# MCU.net
KiCad netlist of a schematic drawn in Altium Designer
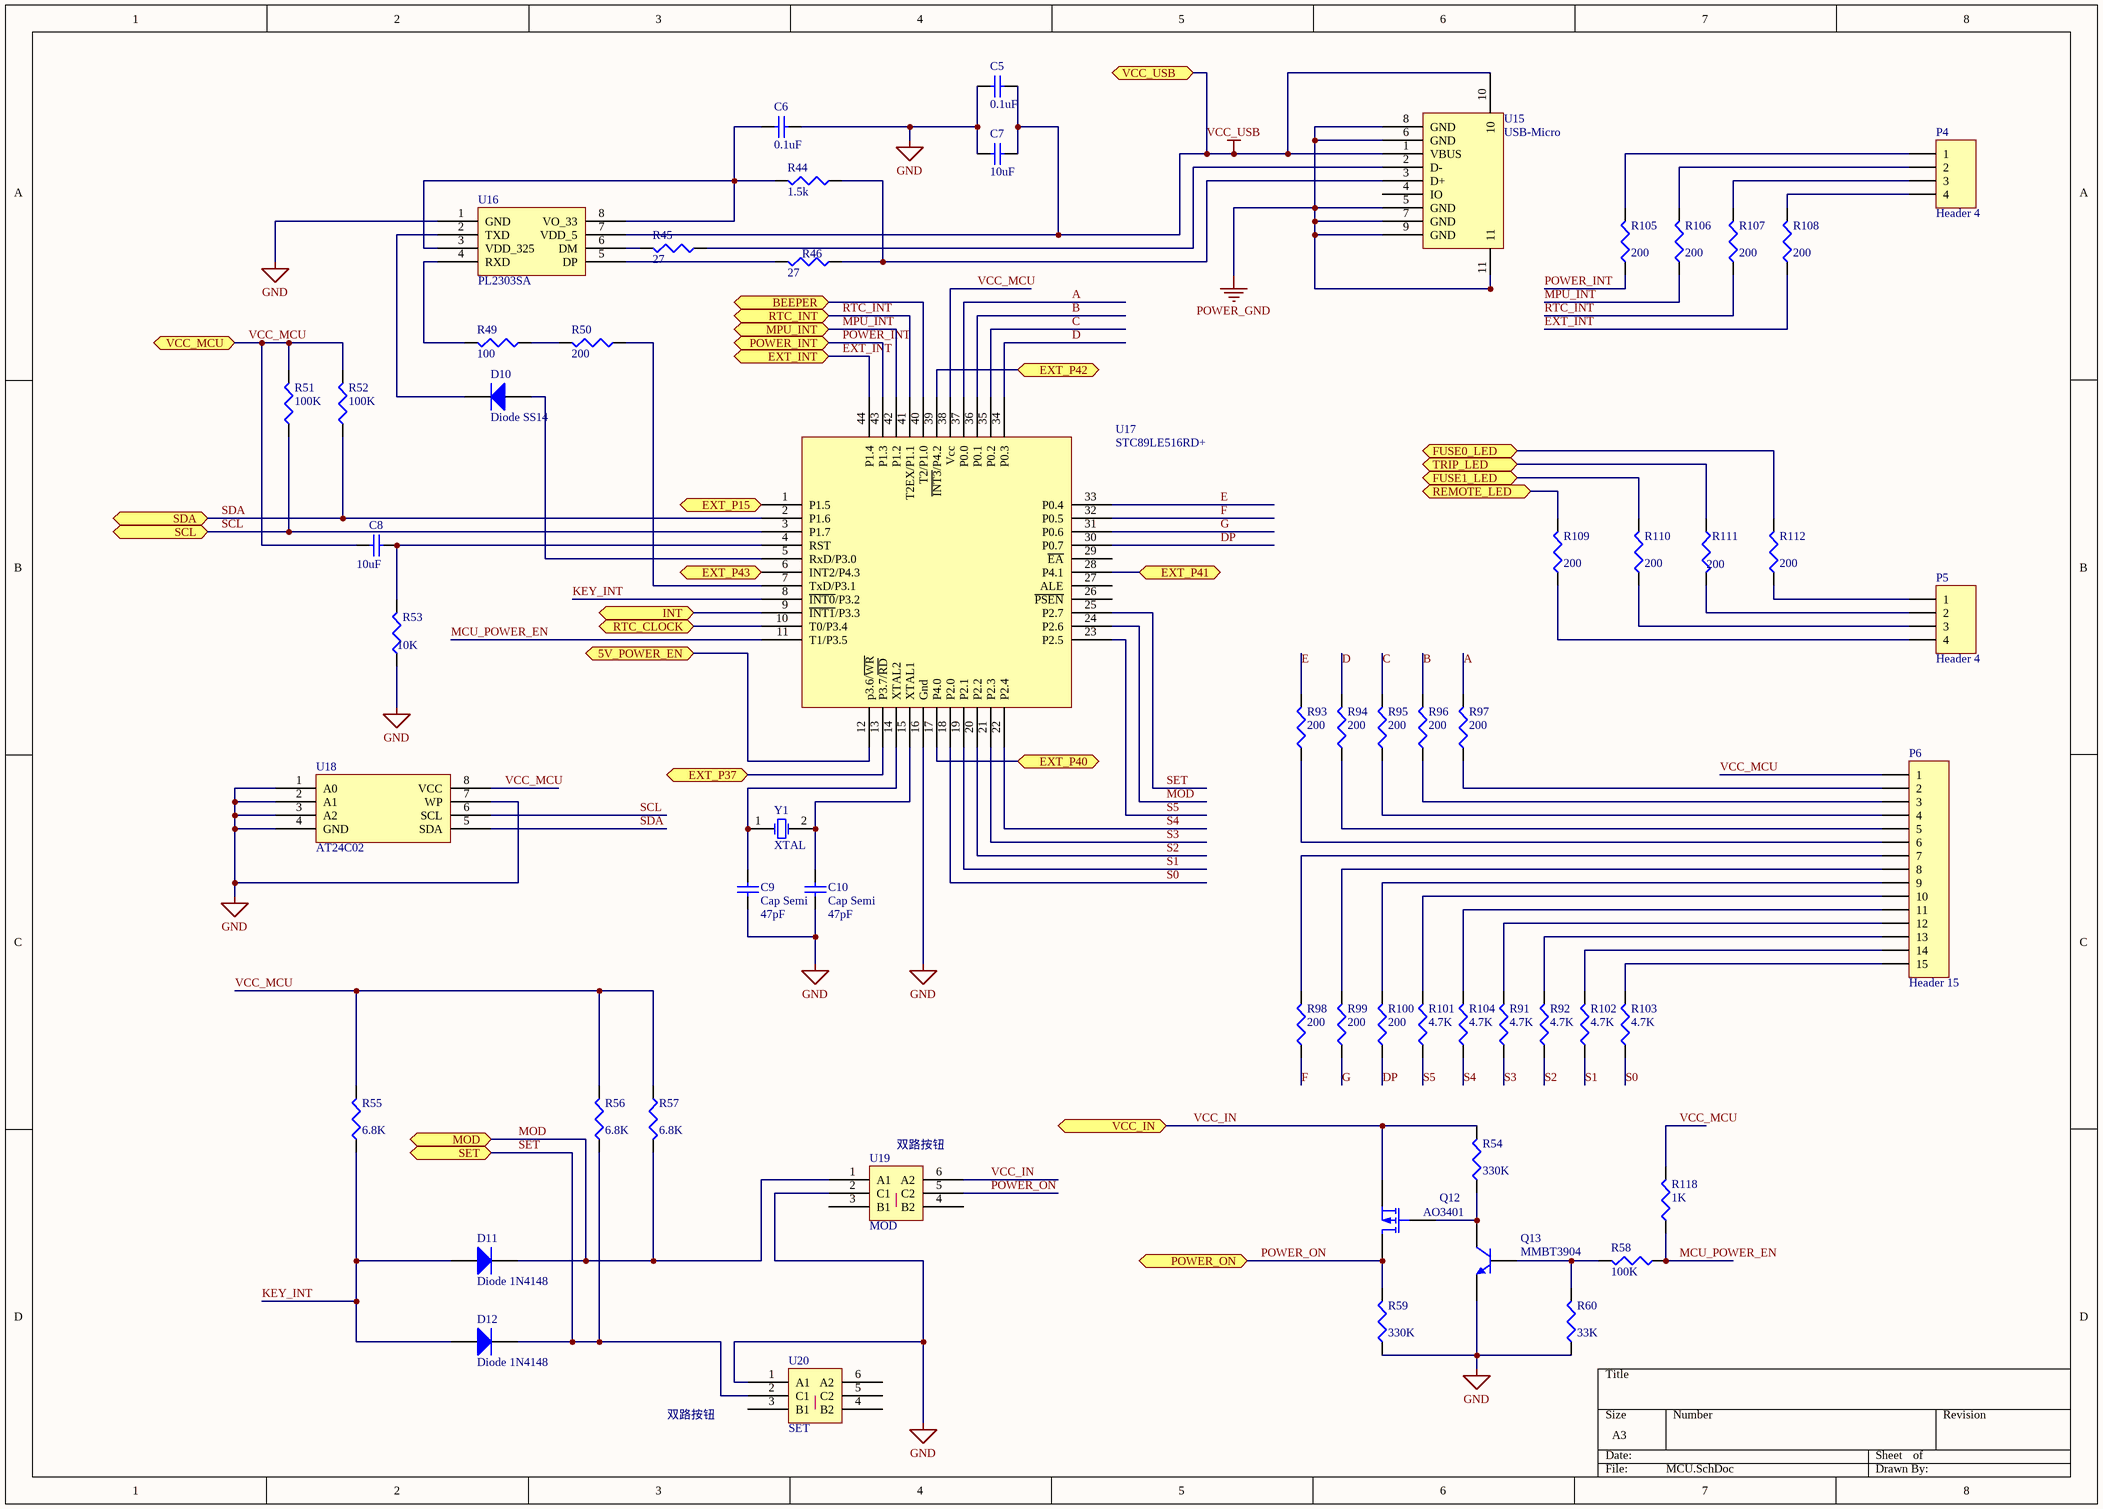
[diagram p0: MCU.SchDoc]

(export (version "E")
  (design (tool "Eeschema 10.0.6"))
  (components
    (comp (ref "C5")
      (value "0.1uF")
      (footprint "clock:0603")
      (description "Capacitor (Semiconductor SIM Model)")
      (fields (field (name "Comment") "Cap Semi") (field (name "PUBLISHER") "Altium Limited"))
      (libsource (lib "Miscellaneous Devices") (part "Cap Semi"))
    )
    (comp (ref "C6")
      (value "0.1uF")
      (footprint "clock:0603")
      (description "Capacitor (Semiconductor SIM Model)")
      (fields (field (name "Comment") "Cap Semi") (field (name "PUBLISHER") "Altium Limited"))
      (libsource (lib "Miscellaneous Devices") (part "Cap Semi"))
    )
    (comp (ref "C7")
      (value "10uF")
      (footprint "clock:0603")
      (description "Capacitor (Semiconductor SIM Model)")
      (fields (field (name "Comment") "Cap Semi") (field (name "PUBLISHER") "Altium Limited"))
      (libsource (lib "Miscellaneous Devices") (part "Cap Semi"))
    )
    (comp (ref "C8")
      (value "10uF")
      (footprint "clock:0603")
      (description "Capacitor (Semiconductor SIM Model)")
      (fields (field (name "Comment") "Cap Semi") (field (name "PUBLISHER") "Altium Limited"))
      (libsource (lib "Miscellaneous Devices") (part "Cap Semi"))
    )
    (comp (ref "C9")
      (value "Cap Semi")
      (footprint "clock:0603")
      (description "Capacitor (Semiconductor SIM Model)")
      (fields (field (name "ALTIUM_VALUE") "47pF") (field (name "PUBLISHER") "Altium Limited"))
      (libsource (lib "Miscellaneous Devices") (part "Cap Semi"))
    )
    (comp (ref "C10")
      (value "Cap Semi")
      (footprint "clock:0603")
      (description "Capacitor (Semiconductor SIM Model)")
      (fields (field (name "ALTIUM_VALUE") "47pF") (field (name "PUBLISHER") "Altium Limited"))
      (libsource (lib "Miscellaneous Devices") (part "Cap Semi"))
    )
    (comp (ref "D10")
      (value "Diode SS14")
      (footprint "clock:SMA")
      (description "1 Amp General Purpose Rectifier")
      (fields (field (name "PUBLISHER") "Altium Limited"))
      (libsource (lib "Miscellaneous Devices") (part "Diode 1N4005"))
    )
    (comp (ref "D11")
      (value "Diode 1N4148")
      (footprint "clock:1206D")
      (description "1 Amp General Purpose Rectifier")
      (fields (field (name "PUBLISHER") "Altium Limited"))
      (libsource (lib "Miscellaneous Devices") (part "Diode 1N4005"))
    )
    (comp (ref "D12")
      (value "Diode 1N4148")
      (footprint "clock:1206D")
      (description "1 Amp General Purpose Rectifier")
      (fields (field (name "PUBLISHER") "Altium Limited"))
      (libsource (lib "Miscellaneous Devices") (part "Diode 1N4005"))
    )
    (comp (ref "P4")
      (value "Header 4")
      (footprint "HDR1X4")
      (description "Header, 4-Pin")
      (fields (field (name "PUBLISHER") "Altium Limited"))
      (libsource (lib "Miscellaneous Connectors") (part "Header 4"))
    )
    (comp (ref "P5")
      (value "Header 4")
      (footprint "HDR1X4")
      (description "Header, 4-Pin")
      (fields (field (name "PUBLISHER") "Altium Limited"))
      (libsource (lib "Miscellaneous Connectors") (part "Header 4"))
    )
    (comp (ref "P6")
      (value "Header 15")
      (footprint "clock:HDR1X15")
      (description "Header, 15-Pin")
      (fields (field (name "PUBLISHER") "Altium Limited"))
      (libsource (lib "Miscellaneous Connectors") (part "Header 15"))
    )
    (comp (ref "Q12")
      (value "AO3401")
      (footprint "clock:SOT23-3-PMOS")
      (description "P-Channel MOSFET")
      (fields (field (name "PUBLISHER") "Altium Limited"))
      (libsource (lib "Miscellaneous Devices") (part "MOSFET-P"))
    )
    (comp (ref "Q13")
      (value "MMBT3904")
      (footprint "clock:SOT23-3-NPN")
      (description "NPN General Purpose Amplifier")
      (fields (field (name "PUBLISHER") "Altium Limited"))
      (libsource (lib "Miscellaneous Devices") (part "2N3904"))
    )
    (comp (ref "R44")
      (value "1.5k")
      (footprint "clock:0603")
      (description "Resistor")
      (fields (field (name "Comment") "Res3") (field (name "PUBLISHER") "Altium Limited"))
      (libsource (lib "Miscellaneous Devices") (part "Res3"))
    )
    (comp (ref "R45")
      (value "27")
      (footprint "clock:0603")
      (description "Resistor")
      (fields (field (name "Comment") "Res3") (field (name "PUBLISHER") "Altium Limited"))
      (libsource (lib "Miscellaneous Devices") (part "Res3"))
    )
    (comp (ref "R46")
      (value "27")
      (footprint "clock:0603")
      (description "Resistor")
      (fields (field (name "Comment") "Res3") (field (name "PUBLISHER") "Altium Limited"))
      (libsource (lib "Miscellaneous Devices") (part "Res3"))
    )
    (comp (ref "R49")
      (value "100")
      (footprint "clock:0603")
      (description "Resistor")
      (fields (field (name "Comment") "Res3") (field (name "PUBLISHER") "Altium Limited"))
      (libsource (lib "Miscellaneous Devices") (part "Res3"))
    )
    (comp (ref "R50")
      (value "200")
      (footprint "clock:0603")
      (description "Resistor")
      (fields (field (name "Comment") "Res3") (field (name "PUBLISHER") "Altium Limited"))
      (libsource (lib "Miscellaneous Devices") (part "Res3"))
    )
    (comp (ref "R51")
      (value "100K")
      (footprint "clock:0603")
      (description "Resistor")
      (fields (field (name "Comment") "Res3") (field (name "PUBLISHER") "Altium Limited"))
      (libsource (lib "Miscellaneous Devices") (part "Res3"))
    )
    (comp (ref "R52")
      (value "100K")
      (footprint "clock:0603")
      (description "Resistor")
      (fields (field (name "Comment") "Res3") (field (name "PUBLISHER") "Altium Limited"))
      (libsource (lib "Miscellaneous Devices") (part "Res3"))
    )
    (comp (ref "R53")
      (value "10K")
      (footprint "clock:0603")
      (description "Resistor")
      (fields (field (name "Comment") "Res3") (field (name "PUBLISHER") "Altium Limited"))
      (libsource (lib "Miscellaneous Devices") (part "Res3"))
    )
    (comp (ref "R54")
      (value "330K")
      (footprint "clock:0603")
      (description "Resistor")
      (fields (field (name "Comment") "Res3") (field (name "PUBLISHER") "Altium Limited"))
      (libsource (lib "Miscellaneous Devices") (part "Res3"))
    )
    (comp (ref "R55")
      (value "6.8K")
      (footprint "clock:0603")
      (description "Resistor")
      (fields (field (name "Comment") "Res3") (field (name "PUBLISHER") "Altium Limited"))
      (libsource (lib "Miscellaneous Devices") (part "Res3"))
    )
    (comp (ref "R56")
      (value "6.8K")
      (footprint "clock:0603")
      (description "Resistor")
      (fields (field (name "Comment") "Res3") (field (name "PUBLISHER") "Altium Limited"))
      (libsource (lib "Miscellaneous Devices") (part "Res3"))
    )
    (comp (ref "R57")
      (value "6.8K")
      (footprint "clock:0603")
      (description "Resistor")
      (fields (field (name "Comment") "Res3") (field (name "PUBLISHER") "Altium Limited"))
      (libsource (lib "Miscellaneous Devices") (part "Res3"))
    )
    (comp (ref "R58")
      (value "100K")
      (footprint "clock:0603")
      (description "Resistor")
      (fields (field (name "Comment") "Res3") (field (name "PUBLISHER") "Altium Limited"))
      (libsource (lib "Miscellaneous Devices") (part "Res3"))
    )
    (comp (ref "R59")
      (value "330K")
      (footprint "clock:0603")
      (description "Resistor")
      (fields (field (name "Comment") "Res3") (field (name "PUBLISHER") "Altium Limited"))
      (libsource (lib "Miscellaneous Devices") (part "Res3"))
    )
    (comp (ref "R60")
      (value "33K")
      (footprint "clock:0603")
      (description "Resistor")
      (fields (field (name "Comment") "Res3") (field (name "PUBLISHER") "Altium Limited"))
      (libsource (lib "Miscellaneous Devices") (part "Res3"))
    )
    (comp (ref "R91")
      (value "4.7K")
      (footprint "clock:0603")
      (description "Resistor")
      (fields (field (name "Comment") "Res3") (field (name "PUBLISHER") "Altium Limited"))
      (libsource (lib "Miscellaneous Devices") (part "Res3"))
    )
    (comp (ref "R92")
      (value "4.7K")
      (footprint "clock:0603")
      (description "Resistor")
      (fields (field (name "Comment") "Res3") (field (name "PUBLISHER") "Altium Limited"))
      (libsource (lib "Miscellaneous Devices") (part "Res3"))
    )
    (comp (ref "R93")
      (value "200")
      (footprint "clock:0603")
      (description "Resistor")
      (fields (field (name "Comment") "Res3") (field (name "PUBLISHER") "Altium Limited"))
      (libsource (lib "Miscellaneous Devices") (part "Res3"))
    )
    (comp (ref "R94")
      (value "200")
      (footprint "clock:0603")
      (description "Resistor")
      (fields (field (name "Comment") "Res3") (field (name "PUBLISHER") "Altium Limited"))
      (libsource (lib "Miscellaneous Devices") (part "Res3"))
    )
    (comp (ref "R95")
      (value "200")
      (footprint "clock:0603")
      (description "Resistor")
      (fields (field (name "Comment") "Res3") (field (name "PUBLISHER") "Altium Limited"))
      (libsource (lib "Miscellaneous Devices") (part "Res3"))
    )
    (comp (ref "R96")
      (value "200")
      (footprint "clock:0603")
      (description "Resistor")
      (fields (field (name "Comment") "Res3") (field (name "PUBLISHER") "Altium Limited"))
      (libsource (lib "Miscellaneous Devices") (part "Res3"))
    )
    (comp (ref "R97")
      (value "200")
      (footprint "clock:0603")
      (description "Resistor")
      (fields (field (name "Comment") "Res3") (field (name "PUBLISHER") "Altium Limited"))
      (libsource (lib "Miscellaneous Devices") (part "Res3"))
    )
    (comp (ref "R98")
      (value "200")
      (footprint "clock:0603")
      (description "Resistor")
      (fields (field (name "Comment") "Res3") (field (name "PUBLISHER") "Altium Limited"))
      (libsource (lib "Miscellaneous Devices") (part "Res3"))
    )
    (comp (ref "R99")
      (value "200")
      (footprint "clock:0603")
      (description "Resistor")
      (fields (field (name "Comment") "Res3") (field (name "PUBLISHER") "Altium Limited"))
      (libsource (lib "Miscellaneous Devices") (part "Res3"))
    )
    (comp (ref "R100")
      (value "200")
      (footprint "clock:0603")
      (description "Resistor")
      (fields (field (name "Comment") "Res3") (field (name "PUBLISHER") "Altium Limited"))
      (libsource (lib "Miscellaneous Devices") (part "Res3"))
    )
    (comp (ref "R101")
      (value "4.7K")
      (footprint "clock:0603")
      (description "Resistor")
      (fields (field (name "Comment") "Res3") (field (name "PUBLISHER") "Altium Limited"))
      (libsource (lib "Miscellaneous Devices") (part "Res3"))
    )
    (comp (ref "R102")
      (value "4.7K")
      (footprint "clock:0603")
      (description "Resistor")
      (fields (field (name "Comment") "Res3") (field (name "PUBLISHER") "Altium Limited"))
      (libsource (lib "Miscellaneous Devices") (part "Res3"))
    )
    (comp (ref "R103")
      (value "4.7K")
      (footprint "clock:0603")
      (description "Resistor")
      (fields (field (name "Comment") "Res3") (field (name "PUBLISHER") "Altium Limited"))
      (libsource (lib "Miscellaneous Devices") (part "Res3"))
    )
    (comp (ref "R104")
      (value "4.7K")
      (footprint "clock:0603")
      (description "Resistor")
      (fields (field (name "Comment") "Res3") (field (name "PUBLISHER") "Altium Limited"))
      (libsource (lib "Miscellaneous Devices") (part "Res3"))
    )
    (comp (ref "R105")
      (value "200")
      (footprint "clock:0603")
      (description "Resistor")
      (fields (field (name "Comment") "Res3") (field (name "PUBLISHER") "Altium Limited"))
      (libsource (lib "Miscellaneous Devices") (part "Res3"))
    )
    (comp (ref "R106")
      (value "200")
      (footprint "clock:0603")
      (description "Resistor")
      (fields (field (name "Comment") "Res3") (field (name "PUBLISHER") "Altium Limited"))
      (libsource (lib "Miscellaneous Devices") (part "Res3"))
    )
    (comp (ref "R107")
      (value "200")
      (footprint "clock:0603")
      (description "Resistor")
      (fields (field (name "Comment") "Res3") (field (name "PUBLISHER") "Altium Limited"))
      (libsource (lib "Miscellaneous Devices") (part "Res3"))
    )
    (comp (ref "R108")
      (value "200")
      (footprint "clock:0603")
      (description "Resistor")
      (fields (field (name "Comment") "Res3") (field (name "PUBLISHER") "Altium Limited"))
      (libsource (lib "Miscellaneous Devices") (part "Res3"))
    )
    (comp (ref "R109")
      (value "200")
      (footprint "clock:0603")
      (description "Resistor")
      (fields (field (name "Comment") "Res3") (field (name "PUBLISHER") "Altium Limited"))
      (libsource (lib "Miscellaneous Devices") (part "Res3"))
    )
    (comp (ref "R110")
      (value "200")
      (footprint "clock:0603")
      (description "Resistor")
      (fields (field (name "Comment") "Res3") (field (name "PUBLISHER") "Altium Limited"))
      (libsource (lib "Miscellaneous Devices") (part "Res3"))
    )
    (comp (ref "R111")
      (value "200")
      (footprint "clock:0603")
      (description "Resistor")
      (fields (field (name "Comment") "Res3") (field (name "PUBLISHER") "Altium Limited"))
      (libsource (lib "Miscellaneous Devices") (part "Res3"))
    )
    (comp (ref "R112")
      (value "200")
      (footprint "clock:0603")
      (description "Resistor")
      (fields (field (name "Comment") "Res3") (field (name "PUBLISHER") "Altium Limited"))
      (libsource (lib "Miscellaneous Devices") (part "Res3"))
    )
    (comp (ref "R118")
      (value "1K")
      (footprint "clock:0603")
      (description "Resistor")
      (fields (field (name "Comment") "Res3") (field (name "PUBLISHER") "Altium Limited"))
      (libsource (lib "Miscellaneous Devices") (part "Res3"))
    )
    (comp (ref "U15")
      (value "USB-Micro")
      (footprint "clock:USB-Micro")
      (libsource (lib "clock") (part "USB-Micro"))
    )
    (comp (ref "U16") (value "PL2303SA") (footprint "clock:SOP8") (libsource (lib "clock") (part "PL2303SA")))
    (comp (ref "U17")
      (value "STC89LE516RD+")
      (footprint "clock:LQFP44")
      (libsource (lib "clock") (part "STC89LE516RD+"))
    )
    (comp (ref "U18") (value "AT24C02") (footprint "clock:SOP8") (libsource (lib "clock") (part "AT24C02")))
    (comp (ref "U19") (value "MOD") (footprint "clock:HDR2X3") (libsource (lib "clock") (part "BUTTON")))
    (comp (ref "U20") (value "SET") (footprint "clock:HDR2X3") (libsource (lib "clock") (part "BUTTON")))
    (comp (ref "Y1")
      (value "XTAL")
      (footprint "clock:XTAL")
      (description "Crystal Oscillator")
      (fields (field (name "PUBLISHER") "Altium Limited"))
      (libsource (lib "Miscellaneous Devices") (part "XTAL"))
    )
  )
  (nets
    (net (code "1") (name "/5V_POWER_EN") (class "Default")
      (node (ref "U17") (pin "12") (pinfunction "p3.6/~{WR}_12") (pintype "passive"))
    )
    (net (code "2") (name "/A") (class "Default")
      (node (ref "R97") (pin "2") (pinfunction "2_2") (pintype "passive"))
      (node (ref "U17") (pin "37") (pinfunction "P0.0_37") (pintype "passive"))
    )
    (net (code "3") (name "/B") (class "Default")
      (node (ref "R96") (pin "2") (pinfunction "2_2") (pintype "passive"))
      (node (ref "U17") (pin "36") (pinfunction "P0.1_36") (pintype "passive"))
    )
    (net (code "4") (name "/BEEPER") (class "Default")
      (node (ref "U17") (pin "40") (pinfunction "T2/P1.0_40") (pintype "passive"))
    )
    (net (code "5") (name "/C") (class "Default")
      (node (ref "R95") (pin "2") (pinfunction "2_2") (pintype "passive"))
      (node (ref "U17") (pin "35") (pinfunction "P0.2_35") (pintype "passive"))
    )
    (net (code "6") (name "/D") (class "Default")
      (node (ref "R94") (pin "2") (pinfunction "2_2") (pintype "passive"))
      (node (ref "U17") (pin "34") (pinfunction "P0.3_34") (pintype "passive"))
    )
    (net (code "7") (name "/DP") (class "Default")
      (node (ref "R100") (pin "1") (pinfunction "1_1") (pintype "passive"))
      (node (ref "U17") (pin "30") (pinfunction "P0.7_30") (pintype "passive"))
    )
    (net (code "8") (name "/E") (class "Default")
      (node (ref "R93") (pin "2") (pinfunction "2_2") (pintype "passive"))
      (node (ref "U17") (pin "33") (pinfunction "P0.4_33") (pintype "passive"))
    )
    (net (code "9") (name "/EXT_INT") (class "Default")
      (node (ref "R108") (pin "1") (pinfunction "1_1") (pintype "passive"))
      (node (ref "U17") (pin "44") (pinfunction "P1.4_44") (pintype "passive"))
    )
    (net (code "10") (name "/EXT_P15") (class "Default")
      (node (ref "U17") (pin "1") (pinfunction "P1.5_1") (pintype "passive"))
    )
    (net (code "11") (name "/EXT_P37") (class "Default")
      (node (ref "U17") (pin "13") (pinfunction "P3.7/~{RD}_13") (pintype "passive"))
    )
    (net (code "12") (name "/EXT_P40") (class "Default")
      (node (ref "U17") (pin "17") (pinfunction "P4.0_17") (pintype "passive"))
    )
    (net (code "13") (name "/EXT_P41") (class "Default")
      (node (ref "U17") (pin "28") (pinfunction "P4.1_28") (pintype "passive"))
    )
    (net (code "14") (name "/EXT_P42") (class "Default")
      (node (ref "U17") (pin "39") (pinfunction "~{INT3}/P4.2_39") (pintype "passive"))
    )
    (net (code "15") (name "/EXT_P43") (class "Default")
      (node (ref "U17") (pin "6") (pinfunction "INT2/P4.3_6") (pintype "passive"))
    )
    (net (code "16") (name "/F") (class "Default")
      (node (ref "R98") (pin "1") (pinfunction "1_1") (pintype "passive"))
      (node (ref "U17") (pin "32") (pinfunction "P0.5_32") (pintype "passive"))
    )
    (net (code "17") (name "/FUSE0_LED") (class "Default")
      (node (ref "R112") (pin "2") (pinfunction "2_2") (pintype "passive"))
    )
    (net (code "18") (name "/FUSE1_LED") (class "Default")
      (node (ref "R110") (pin "2") (pinfunction "2_2") (pintype "passive"))
    )
    (net (code "19") (name "/G") (class "Default")
      (node (ref "R99") (pin "1") (pinfunction "1_1") (pintype "passive"))
      (node (ref "U17") (pin "31") (pinfunction "P0.6_31") (pintype "passive"))
    )
    (net (code "20") (name "/INT") (class "Default")
      (node (ref "U17") (pin "9") (pinfunction "~{INT1}/P3.3_9") (pintype "passive"))
    )
    (net (code "21") (name "/KEY_INT") (class "Default")
      (node (ref "D11") (pin "1") (pinfunction "A_1") (pintype "passive"))
      (node (ref "D12") (pin "1") (pinfunction "A_1") (pintype "passive"))
      (node (ref "R55") (pin "1") (pinfunction "1_1") (pintype "passive"))
      (node (ref "U17") (pin "8") (pinfunction "~{INT0}/P3.2_8") (pintype "passive"))
    )
    (net (code "22") (name "/MCU_POWER_EN") (class "Default")
      (node (ref "R118") (pin "1") (pinfunction "1_1") (pintype "passive"))
      (node (ref "R58") (pin "1") (pinfunction "1_1") (pintype "passive"))
      (node (ref "U17") (pin "11") (pinfunction "T1/P3.5_11") (pintype "passive"))
    )
    (net (code "23") (name "/MOD") (class "Default")
      (node (ref "D11") (pin "2") (pinfunction "K_2") (pintype "passive"))
      (node (ref "R57") (pin "2") (pinfunction "2_2") (pintype "passive"))
      (node (ref "U17") (pin "24") (pinfunction "P2.6_24") (pintype "passive"))
      (node (ref "U19") (pin "1") (pinfunction "A1_1") (pintype "passive"))
    )
    (net (code "24") (name "/MPU_INT") (class "Default")
      (node (ref "R106") (pin "1") (pinfunction "1_1") (pintype "passive"))
      (node (ref "U17") (pin "42") (pinfunction "P1.2_42") (pintype "passive"))
    )
    (net (code "25") (name "/POWER_INT") (class "Default")
      (node (ref "R105") (pin "1") (pinfunction "1_1") (pintype "passive"))
      (node (ref "U17") (pin "43") (pinfunction "P1.3_43") (pintype "passive"))
    )
    (net (code "26") (name "/POWER_ON") (class "Default")
      (node (ref "Q12") (pin "1") (pinfunction "D_1") (pintype "passive"))
      (node (ref "R59") (pin "2") (pinfunction "2_2") (pintype "passive"))
      (node (ref "U19") (pin "5") (pinfunction "C2_5") (pintype "passive"))
    )
    (net (code "27") (name "/REMOTE_LED") (class "Default")
      (node (ref "R109") (pin "2") (pinfunction "2_2") (pintype "passive"))
    )
    (net (code "28") (name "/RTC_CLOCK") (class "Default")
      (node (ref "U17") (pin "10") (pinfunction "T0/P3.4_10") (pintype "passive"))
    )
    (net (code "29") (name "/RTC_INT") (class "Default")
      (node (ref "R107") (pin "1") (pinfunction "1_1") (pintype "passive"))
      (node (ref "U17") (pin "41") (pinfunction "T2EX/P1.1_41") (pintype "passive"))
    )
    (net (code "30") (name "/S0") (class "Default")
      (node (ref "R103") (pin "1") (pinfunction "1_1") (pintype "passive"))
      (node (ref "U17") (pin "18") (pinfunction "P2.0_18") (pintype "passive"))
    )
    (net (code "31") (name "/S1") (class "Default")
      (node (ref "R102") (pin "1") (pinfunction "1_1") (pintype "passive"))
      (node (ref "U17") (pin "19") (pinfunction "P2.1_19") (pintype "passive"))
    )
    (net (code "32") (name "/S2") (class "Default")
      (node (ref "R92") (pin "1") (pinfunction "1_1") (pintype "passive"))
      (node (ref "U17") (pin "20") (pinfunction "P2.2_20") (pintype "passive"))
    )
    (net (code "33") (name "/S3") (class "Default")
      (node (ref "R91") (pin "1") (pinfunction "1_1") (pintype "passive"))
      (node (ref "U17") (pin "21") (pinfunction "P2.3_21") (pintype "passive"))
    )
    (net (code "34") (name "/S4") (class "Default")
      (node (ref "R104") (pin "1") (pinfunction "1_1") (pintype "passive"))
      (node (ref "U17") (pin "22") (pinfunction "P2.4_22") (pintype "passive"))
    )
    (net (code "35") (name "/S5") (class "Default")
      (node (ref "R101") (pin "1") (pinfunction "1_1") (pintype "passive"))
      (node (ref "U17") (pin "23") (pinfunction "P2.5_23") (pintype "passive"))
    )
    (net (code "36") (name "/SCL") (class "Default")
      (node (ref "R51") (pin "1") (pinfunction "1_1") (pintype "passive"))
      (node (ref "U17") (pin "3") (pinfunction "P1.7_3") (pintype "passive"))
      (node (ref "U18") (pin "6") (pinfunction "SCL_6") (pintype "passive"))
    )
    (net (code "37") (name "/SDA") (class "Default")
      (node (ref "R52") (pin "1") (pinfunction "1_1") (pintype "passive"))
      (node (ref "U17") (pin "2") (pinfunction "P1.6_2") (pintype "passive"))
      (node (ref "U18") (pin "5") (pinfunction "SDA_5") (pintype "passive"))
    )
    (net (code "38") (name "/SET") (class "Default")
      (node (ref "D12") (pin "2") (pinfunction "K_2") (pintype "passive"))
      (node (ref "R56") (pin "1") (pinfunction "1_1") (pintype "passive"))
      (node (ref "U17") (pin "25") (pinfunction "P2.7_25") (pintype "passive"))
      (node (ref "U20") (pin "2") (pinfunction "C1_2") (pintype "passive"))
    )
    (net (code "39") (name "/TRIP_LED") (class "Default")
      (node (ref "R111") (pin "1") (pinfunction "1_1") (pintype "passive"))
    )
    (net (code "40") (name "/VCC_IN") (class "Default")
      (node (ref "Q12") (pin "3") (pinfunction "S_3") (pintype "passive"))
      (node (ref "R54") (pin "2") (pinfunction "2_2") (pintype "passive"))
      (node (ref "U19") (pin "6") (pinfunction "A2_6") (pintype "passive"))
    )
    (net (code "41") (name "/VCC_MCU") (class "Default")
      (node (ref "C8") (pin "2") (pinfunction "2_2") (pintype "passive"))
      (node (ref "P6") (pin "1") (pinfunction "1_1") (pintype "passive"))
      (node (ref "R118") (pin "2") (pinfunction "2_2") (pintype "passive"))
      (node (ref "R51") (pin "2") (pinfunction "2_2") (pintype "passive"))
      (node (ref "R52") (pin "2") (pinfunction "2_2") (pintype "passive"))
      (node (ref "R55") (pin "2") (pinfunction "2_2") (pintype "passive"))
      (node (ref "R56") (pin "2") (pinfunction "2_2") (pintype "passive"))
      (node (ref "R57") (pin "1") (pinfunction "1_1") (pintype "passive"))
      (node (ref "U17") (pin "38") (pinfunction "Vcc_38") (pintype "passive"))
      (node (ref "U18") (pin "8") (pinfunction "VCC_8") (pintype "passive"))
    )
    (net (code "42") (name "GND") (class "Default")
      (node (ref "C10") (pin "1") (pinfunction "1_1") (pintype "passive"))
      (node (ref "C5") (pin "1") (pinfunction "1_1") (pintype "passive"))
      (node (ref "C6") (pin "2") (pinfunction "2_2") (pintype "passive"))
      (node (ref "C7") (pin "1") (pinfunction "1_1") (pintype "passive"))
      (node (ref "C9") (pin "1") (pinfunction "1_1") (pintype "passive"))
      (node (ref "Q13") (pin "1") (pinfunction "E_1") (pintype "passive"))
      (node (ref "R53") (pin "1") (pinfunction "1_1") (pintype "passive"))
      (node (ref "R59") (pin "1") (pinfunction "1_1") (pintype "passive"))
      (node (ref "R60") (pin "1") (pinfunction "1_1") (pintype "passive"))
      (node (ref "U16") (pin "1") (pinfunction "GND_1") (pintype "passive"))
      (node (ref "U17") (pin "16") (pinfunction "Gnd_16") (pintype "passive"))
      (node (ref "U18") (pin "1") (pinfunction "A0_1") (pintype "passive"))
      (node (ref "U18") (pin "2") (pinfunction "A1_2") (pintype "passive"))
      (node (ref "U18") (pin "3") (pinfunction "A2_3") (pintype "passive"))
      (node (ref "U18") (pin "4") (pinfunction "GND_4") (pintype "power_in"))
      (node (ref "U18") (pin "7") (pinfunction "WP_7") (pintype "passive"))
      (node (ref "U19") (pin "2") (pinfunction "C1_2") (pintype "passive"))
      (node (ref "U20") (pin "1") (pinfunction "A1_1") (pintype "passive"))
    )
    (net (code "43") (name "Net-(D10-A)") (class "Default")
      (node (ref "D10") (pin "1") (pinfunction "A_1") (pintype "passive"))
      (node (ref "U17") (pin "5") (pinfunction "RxD/P3.0_5") (pintype "passive"))
    )
    (net (code "44") (name "Net-(D10-K)") (class "Default")
      (node (ref "D10") (pin "2") (pinfunction "K_2") (pintype "passive"))
      (node (ref "U16") (pin "2") (pinfunction "TXD_2") (pintype "passive"))
    )
    (net (code "45") (name "Net-(P4-Pad1)") (class "Default")
      (node (ref "P4") (pin "1") (pinfunction "1_1") (pintype "passive"))
      (node (ref "R105") (pin "2") (pinfunction "2_2") (pintype "passive"))
    )
    (net (code "46") (name "Net-(P4-Pad2)") (class "Default")
      (node (ref "P4") (pin "2") (pinfunction "2_2") (pintype "passive"))
      (node (ref "R106") (pin "2") (pinfunction "2_2") (pintype "passive"))
    )
    (net (code "47") (name "Net-(P4-Pad3)") (class "Default")
      (node (ref "P4") (pin "3") (pinfunction "3_3") (pintype "passive"))
      (node (ref "R107") (pin "2") (pinfunction "2_2") (pintype "passive"))
    )
    (net (code "48") (name "Net-(P4-Pad4)") (class "Default")
      (node (ref "P4") (pin "4") (pinfunction "4_4") (pintype "passive"))
      (node (ref "R108") (pin "2") (pinfunction "2_2") (pintype "passive"))
    )
    (net (code "49") (name "Net-(P5-Pad1)") (class "Default")
      (node (ref "P5") (pin "1") (pinfunction "1_1") (pintype "passive"))
      (node (ref "R112") (pin "1") (pinfunction "1_1") (pintype "passive"))
    )
    (net (code "50") (name "Net-(P5-Pad2)") (class "Default")
      (node (ref "P5") (pin "2") (pinfunction "2_2") (pintype "passive"))
      (node (ref "R111") (pin "2") (pinfunction "2_2") (pintype "passive"))
    )
    (net (code "51") (name "Net-(P5-Pad3)") (class "Default")
      (node (ref "P5") (pin "3") (pinfunction "3_3") (pintype "passive"))
      (node (ref "R110") (pin "1") (pinfunction "1_1") (pintype "passive"))
    )
    (net (code "52") (name "Net-(P5-Pad4)") (class "Default")
      (node (ref "P5") (pin "4") (pinfunction "4_4") (pintype "passive"))
      (node (ref "R109") (pin "1") (pinfunction "1_1") (pintype "passive"))
    )
    (net (code "53") (name "Net-(P6-Pad2)") (class "Default")
      (node (ref "P6") (pin "2") (pinfunction "2_2") (pintype "passive"))
      (node (ref "R97") (pin "1") (pinfunction "1_1") (pintype "passive"))
    )
    (net (code "54") (name "Net-(P6-Pad3)") (class "Default")
      (node (ref "P6") (pin "3") (pinfunction "3_3") (pintype "passive"))
      (node (ref "R96") (pin "1") (pinfunction "1_1") (pintype "passive"))
    )
    (net (code "55") (name "Net-(P6-Pad4)") (class "Default")
      (node (ref "P6") (pin "4") (pinfunction "4_4") (pintype "passive"))
      (node (ref "R95") (pin "1") (pinfunction "1_1") (pintype "passive"))
    )
    (net (code "56") (name "Net-(P6-Pad5)") (class "Default")
      (node (ref "P6") (pin "5") (pinfunction "5_5") (pintype "passive"))
      (node (ref "R94") (pin "1") (pinfunction "1_1") (pintype "passive"))
    )
    (net (code "57") (name "Net-(P6-Pad6)") (class "Default")
      (node (ref "P6") (pin "6") (pinfunction "6_6") (pintype "passive"))
      (node (ref "R93") (pin "1") (pinfunction "1_1") (pintype "passive"))
    )
    (net (code "58") (name "Net-(P6-Pad7)") (class "Default")
      (node (ref "P6") (pin "7") (pinfunction "7_7") (pintype "passive"))
      (node (ref "R98") (pin "2") (pinfunction "2_2") (pintype "passive"))
    )
    (net (code "59") (name "Net-(P6-Pad8)") (class "Default")
      (node (ref "P6") (pin "8") (pinfunction "8_8") (pintype "passive"))
      (node (ref "R99") (pin "2") (pinfunction "2_2") (pintype "passive"))
    )
    (net (code "60") (name "Net-(P6-Pad9)") (class "Default")
      (node (ref "P6") (pin "9") (pinfunction "9_9") (pintype "passive"))
      (node (ref "R100") (pin "2") (pinfunction "2_2") (pintype "passive"))
    )
    (net (code "61") (name "Net-(P6-Pad10)") (class "Default")
      (node (ref "P6") (pin "10") (pinfunction "10_10") (pintype "passive"))
      (node (ref "R101") (pin "2") (pinfunction "2_2") (pintype "passive"))
    )
    (net (code "62") (name "Net-(P6-Pad11)") (class "Default")
      (node (ref "P6") (pin "11") (pinfunction "11_11") (pintype "passive"))
      (node (ref "R104") (pin "2") (pinfunction "2_2") (pintype "passive"))
    )
    (net (code "63") (name "Net-(P6-Pad12)") (class "Default")
      (node (ref "P6") (pin "12") (pinfunction "12_12") (pintype "passive"))
      (node (ref "R91") (pin "2") (pinfunction "2_2") (pintype "passive"))
    )
    (net (code "64") (name "Net-(P6-Pad13)") (class "Default")
      (node (ref "P6") (pin "13") (pinfunction "13_13") (pintype "passive"))
      (node (ref "R92") (pin "2") (pinfunction "2_2") (pintype "passive"))
    )
    (net (code "65") (name "Net-(P6-Pad14)") (class "Default")
      (node (ref "P6") (pin "14") (pinfunction "14_14") (pintype "passive"))
      (node (ref "R102") (pin "2") (pinfunction "2_2") (pintype "passive"))
    )
    (net (code "66") (name "Net-(P6-Pad15)") (class "Default")
      (node (ref "P6") (pin "15") (pinfunction "15_15") (pintype "passive"))
      (node (ref "R103") (pin "2") (pinfunction "2_2") (pintype "passive"))
    )
    (net (code "67") (name "Net-(Q12-G)") (class "Default")
      (node (ref "Q12") (pin "2") (pinfunction "G_2") (pintype "passive"))
      (node (ref "Q13") (pin "3") (pinfunction "C_3") (pintype "passive"))
      (node (ref "R54") (pin "1") (pinfunction "1_1") (pintype "passive"))
    )
    (net (code "68") (name "Net-(Q13-B)") (class "Default")
      (node (ref "Q13") (pin "2") (pinfunction "B_2") (pintype "passive"))
      (node (ref "R58") (pin "2") (pinfunction "2_2") (pintype "passive"))
      (node (ref "R60") (pin "2") (pinfunction "2_2") (pintype "passive"))
    )
    (net (code "69") (name "Net-(R49-Pad1)") (class "Default")
      (node (ref "R49") (pin "1") (pinfunction "1_1") (pintype "passive"))
      (node (ref "R50") (pin "2") (pinfunction "2_2") (pintype "passive"))
    )
    (net (code "70") (name "Net-(U15-D+)") (class "Default")
      (node (ref "R44") (pin "1") (pinfunction "1_1") (pintype "passive"))
      (node (ref "R46") (pin "1") (pinfunction "1_1") (pintype "passive"))
      (node (ref "U15") (pin "3") (pinfunction "D+_3") (pintype "passive"))
    )
    (net (code "71") (name "Net-(U15-D-)") (class "Default")
      (node (ref "R45") (pin "1") (pinfunction "1_1") (pintype "passive"))
      (node (ref "U15") (pin "2") (pinfunction "D-_2") (pintype "passive"))
    )
    (net (code "72") (name "Net-(U16-DM)") (class "Default")
      (node (ref "R45") (pin "2") (pinfunction "2_2") (pintype "passive"))
      (node (ref "U16") (pin "6") (pinfunction "DM_6") (pintype "passive"))
    )
    (net (code "73") (name "Net-(U16-DP)") (class "Default")
      (node (ref "R46") (pin "2") (pinfunction "2_2") (pintype "passive"))
      (node (ref "U16") (pin "5") (pinfunction "DP_5") (pintype "passive"))
    )
    (net (code "74") (name "Net-(U16-RXD)") (class "Default")
      (node (ref "R49") (pin "2") (pinfunction "2_2") (pintype "passive"))
      (node (ref "U16") (pin "4") (pinfunction "RXD_4") (pintype "passive"))
    )
    (net (code "75") (name "Net-(U16-VDD_325)") (class "Default")
      (node (ref "C6") (pin "1") (pinfunction "1_1") (pintype "passive"))
      (node (ref "R44") (pin "2") (pinfunction "2_2") (pintype "passive"))
      (node (ref "U16") (pin "3") (pinfunction "VDD_325_3") (pintype "passive"))
      (node (ref "U16") (pin "8") (pinfunction "VO_33_8") (pintype "passive"))
    )
    (net (code "76") (name "Net-(U17-RST)") (class "Default")
      (node (ref "C8") (pin "1") (pinfunction "1_1") (pintype "passive"))
      (node (ref "R53") (pin "2") (pinfunction "2_2") (pintype "passive"))
      (node (ref "U17") (pin "4") (pinfunction "RST_4") (pintype "passive"))
    )
    (net (code "77") (name "Net-(U17-TxD{slash}P3.1)") (class "Default")
      (node (ref "R50") (pin "1") (pinfunction "1_1") (pintype "passive"))
      (node (ref "U17") (pin "7") (pinfunction "TxD/P3.1_7") (pintype "passive"))
    )
    (net (code "78") (name "Net-(U17-XTAL1)") (class "Default")
      (node (ref "C10") (pin "2") (pinfunction "2_2") (pintype "passive"))
      (node (ref "U17") (pin "15") (pinfunction "XTAL1_15") (pintype "passive"))
      (node (ref "Y1") (pin "2") (pinfunction "OSC2_2") (pintype "passive"))
    )
    (net (code "79") (name "Net-(U17-XTAL2)") (class "Default")
      (node (ref "C9") (pin "2") (pinfunction "2_2") (pintype "passive"))
      (node (ref "U17") (pin "14") (pinfunction "XTAL2_14") (pintype "passive"))
      (node (ref "Y1") (pin "1") (pinfunction "OSC1_1") (pintype "passive"))
    )
    (net (code "80") (name "POWER_GND") (class "Default")
      (node (ref "U15") (pin "11") (pinfunction "11_11") (pintype "passive"))
      (node (ref "U15") (pin "5") (pinfunction "GND_5") (pintype "passive"))
      (node (ref "U15") (pin "6") (pinfunction "GND_6") (pintype "passive"))
      (node (ref "U15") (pin "7") (pinfunction "GND_7") (pintype "passive"))
      (node (ref "U15") (pin "8") (pinfunction "GND_8") (pintype "passive"))
      (node (ref "U15") (pin "9") (pinfunction "GND_9") (pintype "passive"))
    )
    (net (code "81") (name "VCC_USB") (class "Default")
      (node (ref "C5") (pin "2") (pinfunction "2_2") (pintype "passive"))
      (node (ref "C7") (pin "2") (pinfunction "2_2") (pintype "passive"))
      (node (ref "U15") (pin "1") (pinfunction "VBUS_1") (pintype "passive"))
      (node (ref "U15") (pin "10") (pinfunction "10_10") (pintype "passive"))
      (node (ref "U16") (pin "7") (pinfunction "VDD_5_7") (pintype "passive"))
    )
    (net (code "82") (name "unconnected-(U15-IO-Pad4)") (class "Default")
      (node (ref "U15") (pin "4") (pinfunction "IO_4") (pintype "passive"))
    )
    (net (code "83") (name "unconnected-(U17-ALE-Pad27)") (class "Default")
      (node (ref "U17") (pin "27") (pinfunction "ALE_27") (pintype "passive"))
    )
    (net (code "84") (name "unconnected-(U17-~{EA}-Pad29)") (class "Default")
      (node (ref "U17") (pin "29") (pinfunction "~{EA}_29") (pintype "passive"))
    )
    (net (code "85") (name "unconnected-(U17-~{PSEN}-Pad26)") (class "Default")
      (node (ref "U17") (pin "26") (pinfunction "~{PSEN}_26") (pintype "passive"))
    )
    (net (code "86") (name "unconnected-(U19-B1-Pad3)") (class "Default")
      (node (ref "U19") (pin "3") (pinfunction "B1_3") (pintype "passive"))
    )
    (net (code "87") (name "unconnected-(U19-B2-Pad4)") (class "Default")
      (node (ref "U19") (pin "4") (pinfunction "B2_4") (pintype "passive"))
    )
    (net (code "88") (name "unconnected-(U20-A2-Pad6)") (class "Default")
      (node (ref "U20") (pin "6") (pinfunction "A2_6") (pintype "passive"))
    )
    (net (code "89") (name "unconnected-(U20-B1-Pad3)") (class "Default")
      (node (ref "U20") (pin "3") (pinfunction "B1_3") (pintype "passive"))
    )
    (net (code "90") (name "unconnected-(U20-B2-Pad4)") (class "Default")
      (node (ref "U20") (pin "4") (pinfunction "B2_4") (pintype "passive"))
    )
    (net (code "91") (name "unconnected-(U20-C2-Pad5)") (class "Default")
      (node (ref "U20") (pin "5") (pinfunction "C2_5") (pintype "passive"))
    )
  )
)
